# 2_Motors_V4.net
KiCad netlist of a schematic drawn in EAGLE
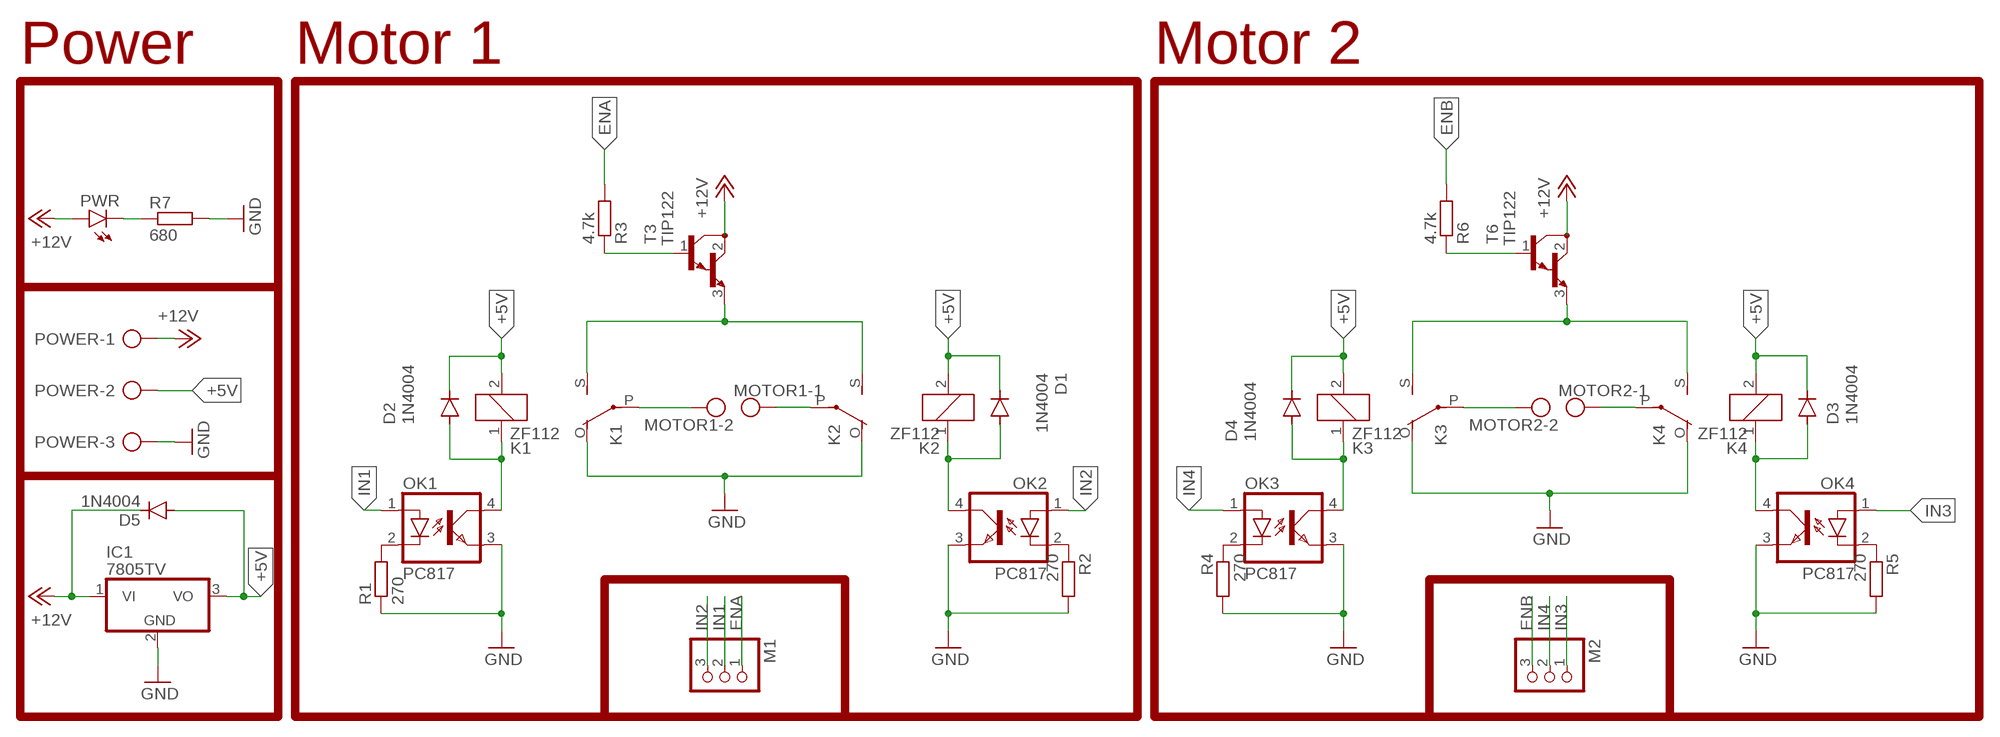
[diagram p0: schematic, sheet 1]

(export (version "E")
  (design (tool "Eeschema 10.0.6"))
  (components
    (comp (ref "D1")
      (value "1N4004")
      (footprint "eagle-import:DO41-10")
      (libsource (lib "eagle-import") (part "1N4004"))
    )
    (comp (ref "D2")
      (value "1N4004")
      (footprint "eagle-import:DO41-10")
      (libsource (lib "eagle-import") (part "1N4004"))
    )
    (comp (ref "D3")
      (value "1N4004")
      (footprint "eagle-import:DO41-10")
      (libsource (lib "eagle-import") (part "1N4004"))
    )
    (comp (ref "D4")
      (value "1N4004")
      (footprint "eagle-import:DO41-10")
      (libsource (lib "eagle-import") (part "1N4004"))
    )
    (comp (ref "D5")
      (value "1N4004")
      (footprint "eagle-import:DO41-10")
      (libsource (lib "eagle-import") (part "1N4004"))
    )
    (comp (ref "IC1")
      (value "7805TV")
      (footprint "eagle-import:TO220V")
      (libsource (lib "eagle-import") (part "78TV05"))
    )
    (comp (ref "K1")
      (value "ZF112")
      (footprint "eagle-import:ZF112")
      (libsource (lib "eagle-import") (part "ZF112"))
    )
    (comp (ref "K2")
      (value "ZF112")
      (footprint "eagle-import:ZF112")
      (libsource (lib "eagle-import") (part "ZF112"))
    )
    (comp (ref "K3")
      (value "ZF112")
      (footprint "eagle-import:ZF112")
      (libsource (lib "eagle-import") (part "ZF112"))
    )
    (comp (ref "K4")
      (value "ZF112")
      (footprint "eagle-import:ZF112")
      (libsource (lib "eagle-import") (part "ZF112"))
    )
    (comp (ref "M1")
      (value "PINHD-1X3")
      (footprint "eagle-import:1X03")
      (libsource (lib "eagle-import") (part "PINHD-1X3"))
    )
    (comp (ref "M2")
      (value "PINHD-1X3")
      (footprint "eagle-import:1X03")
      (libsource (lib "eagle-import") (part "PINHD-1X3"))
    )
    (comp (ref "MOTOR1")
      (value "AK300/2")
      (footprint "eagle-import:AK300_2")
      (libsource (lib "eagle-import") (part "AK300/2"))
    )
    (comp (ref "MOTOR2")
      (value "AK300/2")
      (footprint "eagle-import:AK300_2")
      (libsource (lib "eagle-import") (part "AK300/2"))
    )
    (comp (ref "OK1")
      (value "PC817")
      (footprint "eagle-import:DIL04")
      (fields (field (name "MPN") "PC817X4J000F"))
      (libsource (lib "eagle-import") (part "PC817"))
    )
    (comp (ref "OK2")
      (value "PC817")
      (footprint "eagle-import:DIL04")
      (fields (field (name "MPN") "PC817X4J000F"))
      (libsource (lib "eagle-import") (part "PC817"))
    )
    (comp (ref "OK3")
      (value "PC817")
      (footprint "eagle-import:DIL04")
      (fields (field (name "MPN") "PC817X4J000F"))
      (libsource (lib "eagle-import") (part "PC817"))
    )
    (comp (ref "OK4")
      (value "PC817")
      (footprint "eagle-import:DIL04")
      (fields (field (name "MPN") "PC817X4J000F"))
      (libsource (lib "eagle-import") (part "PC817"))
    )
    (comp (ref "POWER")
      (value "AK300/3")
      (footprint "eagle-import:AK300_3")
      (libsource (lib "eagle-import") (part "AK300/3"))
    )
    (comp (ref "PWR")
      (value "LED5MM")
      (footprint "eagle-import:LED5MM")
      (libsource (lib "eagle-import") (part "LED5MM"))
    )
    (comp (ref "R1")
      (value "270")
      (footprint "eagle-import:0204_7")
      (libsource (lib "eagle-import") (part "R-EU_0204/7"))
    )
    (comp (ref "R2")
      (value "270")
      (footprint "eagle-import:0204_7")
      (libsource (lib "eagle-import") (part "R-EU_0204/7"))
    )
    (comp (ref "R3")
      (value "4.7k")
      (footprint "eagle-import:0204_7")
      (libsource (lib "eagle-import") (part "R-EU_0204/7"))
    )
    (comp (ref "R4")
      (value "270")
      (footprint "eagle-import:0204_7")
      (libsource (lib "eagle-import") (part "R-EU_0204/7"))
    )
    (comp (ref "R5")
      (value "270")
      (footprint "eagle-import:0204_7")
      (libsource (lib "eagle-import") (part "R-EU_0204/7"))
    )
    (comp (ref "R6")
      (value "4.7k")
      (footprint "eagle-import:0204_7")
      (libsource (lib "eagle-import") (part "R-EU_0204/7"))
    )
    (comp (ref "R7")
      (value "680")
      (footprint "eagle-import:0204_7")
      (libsource (lib "eagle-import") (part "R-EU_0204/7"))
    )
    (comp (ref "T3")
      (value "TIP122")
      (footprint "eagle-import:TO220")
      (libsource (lib "eagle-import") (part "TIP122"))
    )
    (comp (ref "T6")
      (value "TIP122")
      (footprint "eagle-import:TO220")
      (libsource (lib "eagle-import") (part "TIP122"))
    )
  )
  (nets
    (net (code "1") (name "+5V") (class "Default")
      (node (ref "D1") (pin "C") (pinfunction "C_C") (pintype "passive"))
      (node (ref "D2") (pin "C") (pinfunction "C_C") (pintype "passive"))
      (node (ref "D3") (pin "C") (pinfunction "C_C") (pintype "passive"))
      (node (ref "D4") (pin "C") (pinfunction "C_C") (pintype "passive"))
      (node (ref "D5") (pin "A") (pinfunction "A_A") (pintype "passive"))
      (node (ref "IC1") (pin "3") (pinfunction "VO_3") (pintype "passive"))
      (node (ref "K1") (pin "2") (pinfunction "2_2") (pintype "passive"))
      (node (ref "K2") (pin "2") (pinfunction "2_2") (pintype "passive"))
      (node (ref "K3") (pin "2") (pinfunction "2_2") (pintype "passive"))
      (node (ref "K4") (pin "2") (pinfunction "2_2") (pintype "passive"))
      (node (ref "POWER") (pin "2") (pinfunction "KL_2") (pintype "passive"))
    )
    (net (code "2") (name "+12V") (class "Default")
      (node (ref "D5") (pin "C") (pinfunction "C_C") (pintype "passive"))
      (node (ref "IC1") (pin "1") (pinfunction "VI_1") (pintype "input"))
      (node (ref "POWER") (pin "1") (pinfunction "KL_1") (pintype "passive"))
      (node (ref "PWR") (pin "A") (pinfunction "A_A") (pintype "passive"))
      (node (ref "T3") (pin "2") (pinfunction "C_2") (pintype "passive"))
      (node (ref "T6") (pin "2") (pinfunction "C_2") (pintype "passive"))
    )
    (net (code "3") (name "ENA") (class "Default")
      (node (ref "M1") (pin "1") (pinfunction "1_1") (pintype "passive"))
      (node (ref "R3") (pin "2") (pinfunction "2_2") (pintype "passive"))
    )
    (net (code "4") (name "ENB") (class "Default")
      (node (ref "M2") (pin "3") (pinfunction "3_3") (pintype "passive"))
      (node (ref "R6") (pin "2") (pinfunction "2_2") (pintype "passive"))
    )
    (net (code "5") (name "GND") (class "Default")
      (node (ref "IC1") (pin "2") (pinfunction "GND_2") (pintype "passive"))
      (node (ref "K1") (pin "O") (pinfunction "O_O") (pintype "passive"))
      (node (ref "K2") (pin "O") (pinfunction "O_O") (pintype "passive"))
      (node (ref "K3") (pin "O") (pinfunction "O_O") (pintype "passive"))
      (node (ref "K4") (pin "O") (pinfunction "O_O") (pintype "passive"))
      (node (ref "OK1") (pin "3") (pinfunction "EMIT_3") (pintype "passive"))
      (node (ref "OK2") (pin "3") (pinfunction "EMIT_3") (pintype "passive"))
      (node (ref "OK3") (pin "3") (pinfunction "EMIT_3") (pintype "passive"))
      (node (ref "OK4") (pin "3") (pinfunction "EMIT_3") (pintype "passive"))
      (node (ref "POWER") (pin "3") (pinfunction "KL_3") (pintype "passive"))
      (node (ref "R1") (pin "1") (pinfunction "1_1") (pintype "passive"))
      (node (ref "R2") (pin "2") (pinfunction "2_2") (pintype "passive"))
      (node (ref "R4") (pin "2") (pinfunction "2_2") (pintype "passive"))
      (node (ref "R5") (pin "2") (pinfunction "2_2") (pintype "passive"))
      (node (ref "R7") (pin "2") (pinfunction "2_2") (pintype "passive"))
    )
    (net (code "6") (name "IN1") (class "Default")
      (node (ref "M1") (pin "2") (pinfunction "2_2") (pintype "passive"))
      (node (ref "OK1") (pin "1") (pinfunction "A_1") (pintype "passive"))
    )
    (net (code "7") (name "IN2") (class "Default")
      (node (ref "M1") (pin "3") (pinfunction "3_3") (pintype "passive"))
      (node (ref "OK2") (pin "1") (pinfunction "A_1") (pintype "passive"))
    )
    (net (code "8") (name "IN3") (class "Default")
      (node (ref "M2") (pin "1") (pinfunction "1_1") (pintype "passive"))
      (node (ref "OK4") (pin "1") (pinfunction "A_1") (pintype "passive"))
    )
    (net (code "9") (name "IN4") (class "Default")
      (node (ref "M2") (pin "2") (pinfunction "2_2") (pintype "passive"))
      (node (ref "OK3") (pin "1") (pinfunction "A_1") (pintype "passive"))
    )
    (net (code "10") (name "Net-(MOTOR1A-KL)") (class "Default")
      (node (ref "K2") (pin "P") (pinfunction "P_P") (pintype "passive"))
      (node (ref "MOTOR1") (pin "1") (pinfunction "KL_1") (pintype "passive"))
    )
    (net (code "11") (name "Net-(MOTOR1B-KL)") (class "Default")
      (node (ref "K1") (pin "P") (pinfunction "P_P") (pintype "passive"))
      (node (ref "MOTOR1") (pin "2") (pinfunction "KL_2") (pintype "passive"))
    )
    (net (code "12") (name "Net-(MOTOR2A-KL)") (class "Default")
      (node (ref "K4") (pin "P") (pinfunction "P_P") (pintype "passive"))
      (node (ref "MOTOR2") (pin "1") (pinfunction "KL_1") (pintype "passive"))
    )
    (net (code "13") (name "Net-(MOTOR2B-KL)") (class "Default")
      (node (ref "K3") (pin "P") (pinfunction "P_P") (pintype "passive"))
      (node (ref "MOTOR2") (pin "2") (pinfunction "KL_2") (pintype "passive"))
    )
    (net (code "14") (name "Net-(OK1-C)") (class "Default")
      (node (ref "OK1") (pin "2") (pinfunction "C_2") (pintype "passive"))
      (node (ref "R1") (pin "2") (pinfunction "2_2") (pintype "passive"))
    )
    (net (code "15") (name "Net-(OK1-COL)") (class "Default")
      (node (ref "D2") (pin "A") (pinfunction "A_A") (pintype "passive"))
      (node (ref "K1") (pin "1") (pinfunction "1_1") (pintype "passive"))
      (node (ref "OK1") (pin "4") (pinfunction "COL_4") (pintype "passive"))
    )
    (net (code "16") (name "Net-(OK2-C)") (class "Default")
      (node (ref "OK2") (pin "2") (pinfunction "C_2") (pintype "passive"))
      (node (ref "R2") (pin "1") (pinfunction "1_1") (pintype "passive"))
    )
    (net (code "17") (name "Net-(OK2-COL)") (class "Default")
      (node (ref "D1") (pin "A") (pinfunction "A_A") (pintype "passive"))
      (node (ref "K2") (pin "1") (pinfunction "1_1") (pintype "passive"))
      (node (ref "OK2") (pin "4") (pinfunction "COL_4") (pintype "passive"))
    )
    (net (code "18") (name "Net-(OK3-C)") (class "Default")
      (node (ref "OK3") (pin "2") (pinfunction "C_2") (pintype "passive"))
      (node (ref "R4") (pin "1") (pinfunction "1_1") (pintype "passive"))
    )
    (net (code "19") (name "Net-(OK3-COL)") (class "Default")
      (node (ref "D4") (pin "A") (pinfunction "A_A") (pintype "passive"))
      (node (ref "K3") (pin "1") (pinfunction "1_1") (pintype "passive"))
      (node (ref "OK3") (pin "4") (pinfunction "COL_4") (pintype "passive"))
    )
    (net (code "20") (name "Net-(OK4-C)") (class "Default")
      (node (ref "OK4") (pin "2") (pinfunction "C_2") (pintype "passive"))
      (node (ref "R5") (pin "1") (pinfunction "1_1") (pintype "passive"))
    )
    (net (code "21") (name "Net-(OK4-COL)") (class "Default")
      (node (ref "D3") (pin "A") (pinfunction "A_A") (pintype "passive"))
      (node (ref "K4") (pin "1") (pinfunction "1_1") (pintype "passive"))
      (node (ref "OK4") (pin "4") (pinfunction "COL_4") (pintype "passive"))
    )
    (net (code "22") (name "Net-(PWR-C)") (class "Default")
      (node (ref "PWR") (pin "K") (pinfunction "C_K") (pintype "passive"))
      (node (ref "R7") (pin "1") (pinfunction "1_1") (pintype "passive"))
    )
    (net (code "23") (name "Net-(T3-B)") (class "Default")
      (node (ref "R3") (pin "1") (pinfunction "1_1") (pintype "passive"))
      (node (ref "T3") (pin "1") (pinfunction "B_1") (pintype "passive"))
    )
    (net (code "24") (name "Net-(T3-E)") (class "Default")
      (node (ref "K1") (pin "S") (pinfunction "S_S") (pintype "passive"))
      (node (ref "K2") (pin "S") (pinfunction "S_S") (pintype "passive"))
      (node (ref "T3") (pin "3") (pinfunction "E_3") (pintype "passive"))
    )
    (net (code "25") (name "Net-(T6-B)") (class "Default")
      (node (ref "R6") (pin "1") (pinfunction "1_1") (pintype "passive"))
      (node (ref "T6") (pin "1") (pinfunction "B_1") (pintype "passive"))
    )
    (net (code "26") (name "Net-(T6-E)") (class "Default")
      (node (ref "K3") (pin "S") (pinfunction "S_S") (pintype "passive"))
      (node (ref "K4") (pin "S") (pinfunction "S_S") (pintype "passive"))
      (node (ref "T6") (pin "3") (pinfunction "E_3") (pintype "passive"))
    )
  )
)
